# 04_PCIe.net
KiCad netlist of a schematic drawn in Altium Designer
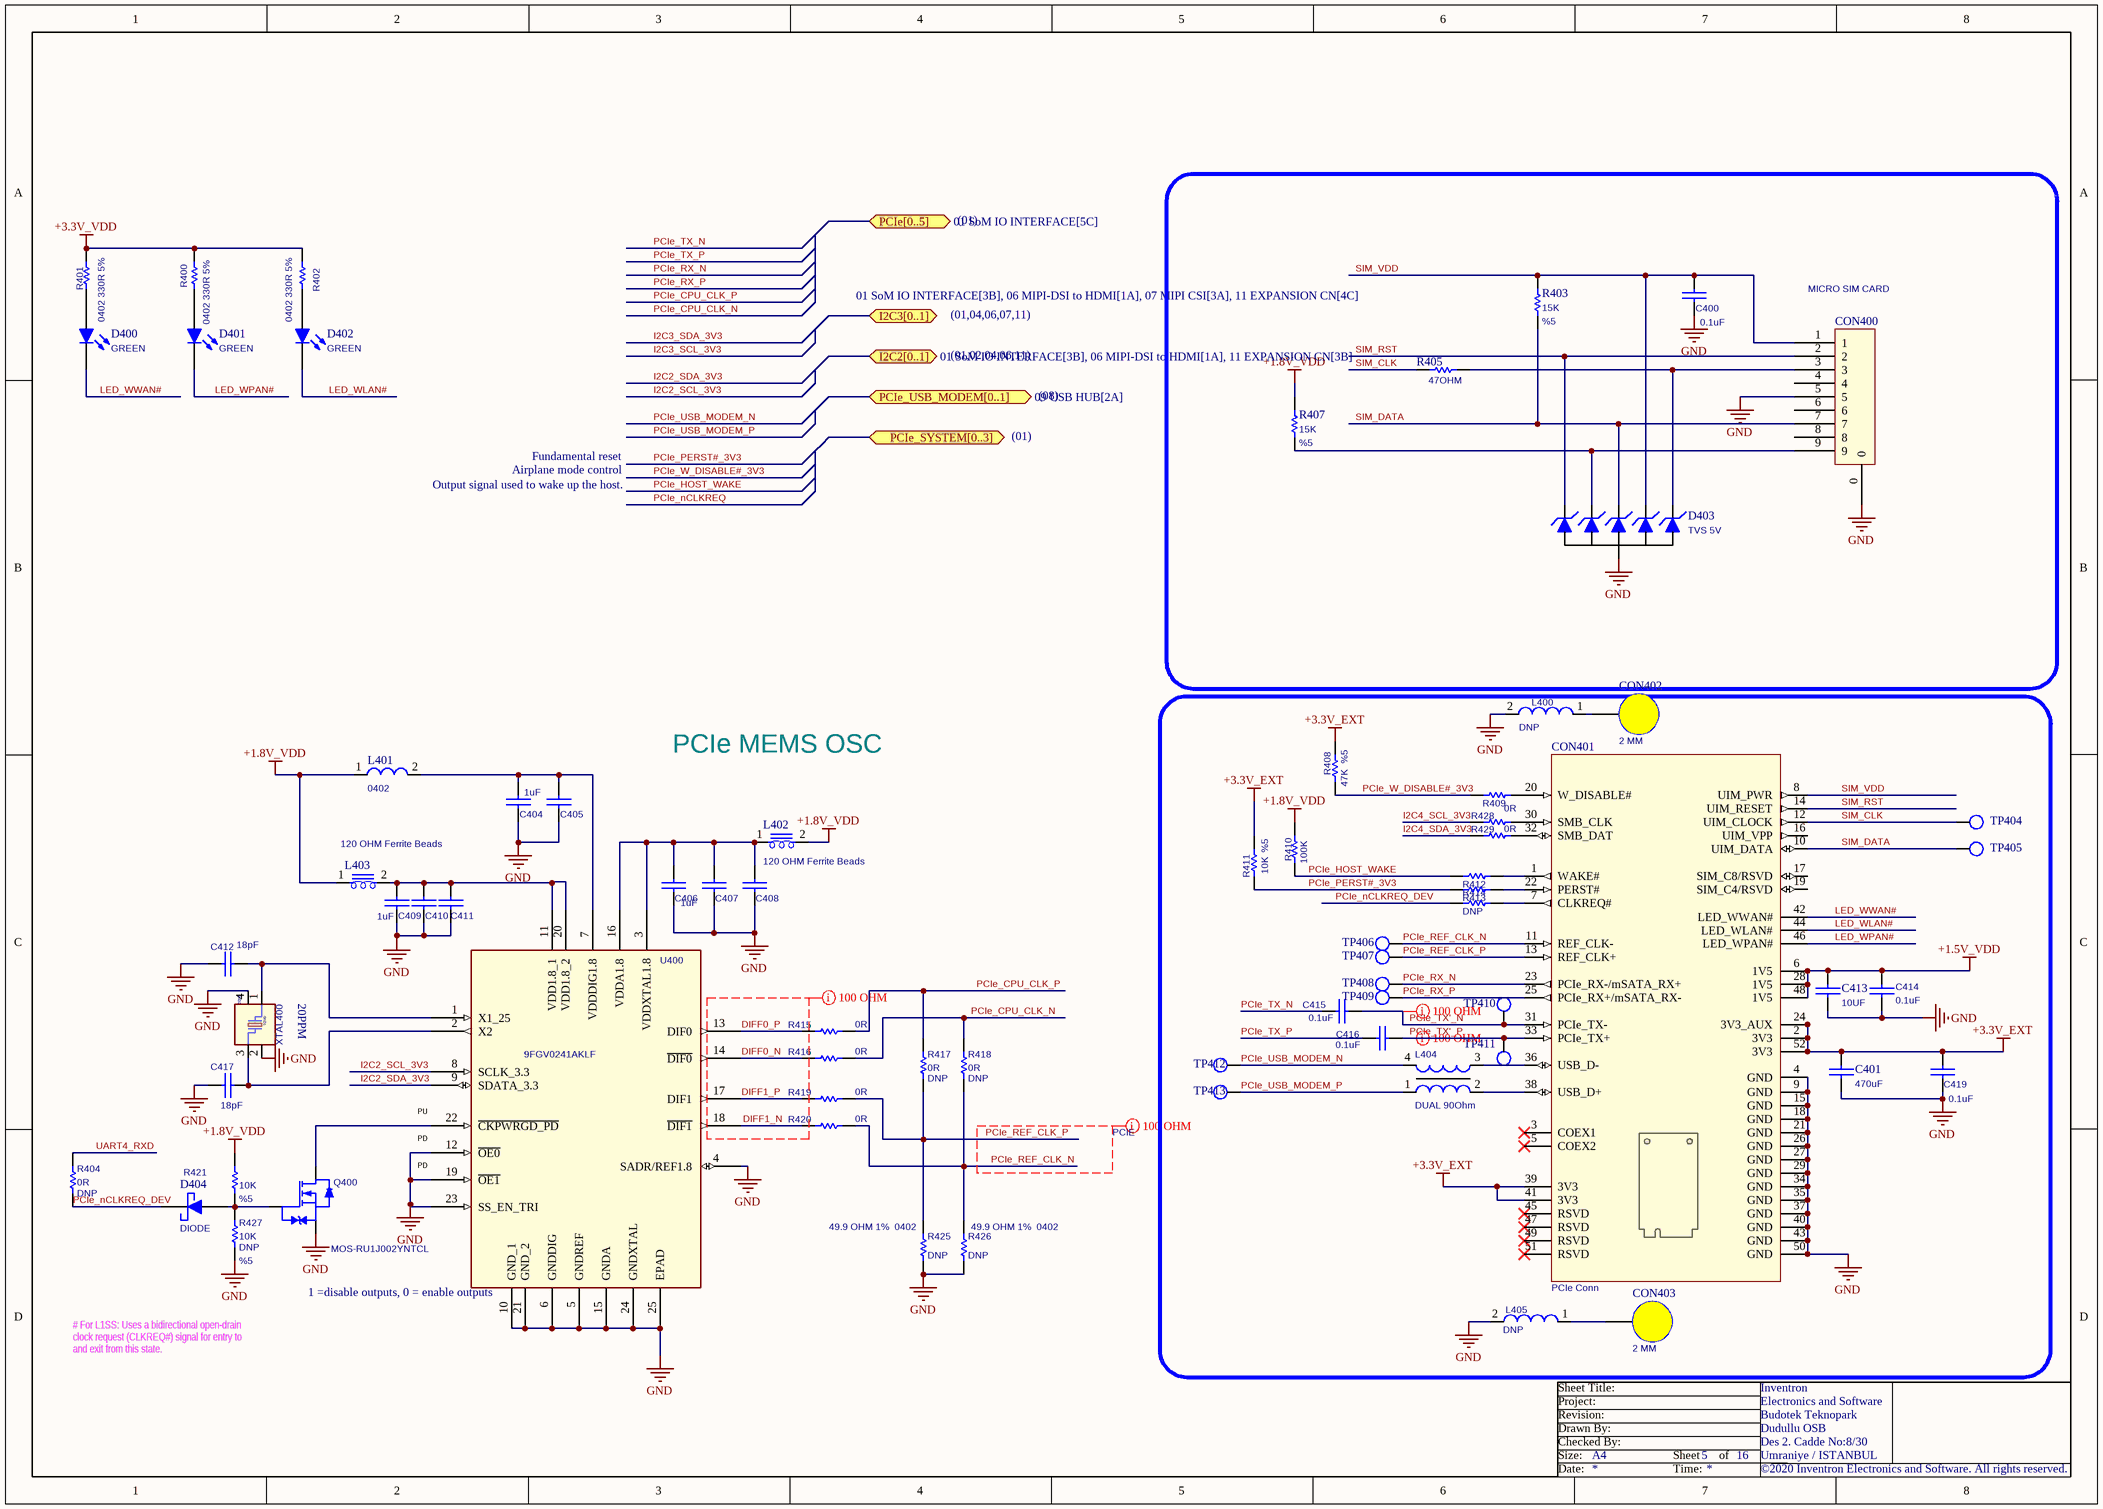
[diagram p0: 04 PCIe.SchDoc]

(export (version "E")
  (design (tool "Eeschema 10.0.6"))
  (components
    (comp (ref "C400")
      (value "0.1uF")
      (footprint "0402_CC")
      (description "CAP VER 0.1UF 16V X7R 0402")
      (fields (field (name "CREATED BY") "LA") (field (name "CHECKED BY") "*"))
      (libsource (lib "ARETE_SCH") (part "CAP-CL05B104KO5NNNC"))
    )
    (comp (ref "C401")
      (value "470uF")
      (footprint "CAP-8.3mm x 8.3mm")
      (description "CAP ALUM 470UF 20% 6.3V SMD")
      (fields (field (name "CREATED BY") "EE") (field (name "CHECKED BY") "*"))
      (libsource (lib "ARETE_SCH") (part "CAP-EEE-FP0J471AP"))
    )
    (comp (ref "C404")
      (value "1uF")
      (footprint "0402_CC")
      (description "CAP CER 1UF 6.3V X6S 0402")
      (fields (field (name "CREATED BY") "LA") (field (name "CHECKED BY") "*"))
      (libsource (lib "ARETE_SCH") (part "CAP-CL05X105KQ5NNNC"))
    )
    (comp (ref "C405")
      (value "0.01uF 16V 0402")
      (footprint "0402_CC")
      (description "CAP CER 10000PF 16V X7R 0402")
      (fields (field (name "CREATED BY") "E.E") (field (name "CHECKED BY") "*"))
      (libsource (lib "ARETE_SCH") (part "CAP-CL05B103KO5NNNC"))
    )
    (comp (ref "C406")
      (value "1uF")
      (footprint "0402_CC")
      (description "CAP CER 1UF 6.3V X6S 0402")
      (fields (field (name "CREATED BY") "LA") (field (name "CHECKED BY") "*"))
      (libsource (lib "ARETE_SCH") (part "CAP-CL05X105KQ5NNNC"))
    )
    (comp (ref "C407")
      (value "0.01uF 16V 0402")
      (footprint "0402_CC")
      (description "CAP CER 10000PF 16V X7R 0402")
      (fields (field (name "CREATED BY") "E.E") (field (name "CHECKED BY") "*"))
      (libsource (lib "ARETE_SCH") (part "CAP-CL05B103KO5NNNC"))
    )
    (comp (ref "C408")
      (value "0.01uF 16V 0402")
      (footprint "0402_CC")
      (description "CAP CER 10000PF 16V X7R 0402")
      (fields (field (name "CREATED BY") "E.E") (field (name "CHECKED BY") "*"))
      (libsource (lib "ARETE_SCH") (part "CAP-CL05B103KO5NNNC"))
    )
    (comp (ref "C409")
      (value "1uF")
      (footprint "0402_CC")
      (description "CAP CER 1UF 6.3V X6S 0402")
      (fields (field (name "CREATED BY") "LA") (field (name "CHECKED BY") "*"))
      (libsource (lib "ARETE_SCH") (part "CAP-CL05X105KQ5NNNC"))
    )
    (comp (ref "C410")
      (value "0.01uF 16V 0402")
      (footprint "0402_CC")
      (description "CAP CER 10000PF 16V X7R 0402")
      (fields (field (name "CREATED BY") "E.E") (field (name "CHECKED BY") "*"))
      (libsource (lib "ARETE_SCH") (part "CAP-CL05B103KO5NNNC"))
    )
    (comp (ref "C411")
      (value "0.01uF 16V 0402")
      (footprint "0402_CC")
      (description "CAP CER 10000PF 16V X7R 0402")
      (fields (field (name "CREATED BY") "E.E") (field (name "CHECKED BY") "*"))
      (libsource (lib "ARETE_SCH") (part "CAP-CL05B103KO5NNNC"))
    )
    (comp (ref "C412")
      (value "18pF")
      (footprint "0402_CC")
      (description "CAP CER 18PF 50V C0G/NPO 0402")
      (fields (field (name "CREATED BY") "LA") (field (name "CHECKED BY") "*"))
      (libsource (lib "ARETE_SCH") (part "CAP-CC0402JRNPO9BN180"))
    )
    (comp (ref "C413")
      (value "10UF")
      (footprint "0805")
      (description "CAP CER 10UF 16V X5R 0805")
      (fields (field (name "CREATED BY") "EE") (field (name "CHECKED BY") "*"))
      (libsource (lib "ARETE_SCH") (part "CAP-CL21A106KOQNNNG"))
    )
    (comp (ref "C414")
      (value "0.1uF")
      (footprint "0402_CC")
      (description "CAP VER 0.1UF 16V X7R 0402")
      (fields (field (name "CREATED BY") "LA") (field (name "CHECKED BY") "*"))
      (libsource (lib "ARETE_SCH") (part "CAP-CL05B104KO5NNNC"))
    )
    (comp (ref "C415")
      (value "0.1uF")
      (footprint "0402_CC")
      (description "CAP VER 0.1UF 16V X7R 0402")
      (fields (field (name "CREATED BY") "LA") (field (name "CHECKED BY") "*"))
      (libsource (lib "ARETE_SCH") (part "CAP-CL05B104KO5NNNC"))
    )
    (comp (ref "C416")
      (value "0.1uF")
      (footprint "0402_CC")
      (description "CAP VER 0.1UF 16V X7R 0402")
      (fields (field (name "CREATED BY") "LA") (field (name "CHECKED BY") "*"))
      (libsource (lib "ARETE_SCH") (part "CAP-CL05B104KO5NNNC"))
    )
    (comp (ref "C417")
      (value "18pF")
      (footprint "0402_CC")
      (description "CAP CER 18PF 50V C0G/NPO 0402")
      (fields (field (name "CREATED BY") "LA") (field (name "CHECKED BY") "*"))
      (libsource (lib "ARETE_SCH") (part "CAP-CC0402JRNPO9BN180"))
    )
    (comp (ref "C419")
      (value "0.1uF")
      (footprint "0402_CC")
      (description "CAP VER 0.1UF 16V X7R 0402")
      (fields (field (name "CREATED BY") "LA") (field (name "CHECKED BY") "*"))
      (libsource (lib "ARETE_SCH") (part "CAP-CL05B104KO5NNNC"))
    )
    (comp (ref "CON400")
      (value "MICRO SIM CARD")
      (footprint "115Q-BCA0")
      (description "CONN.MICRO SIM CARD PUSH PUSH 8+2 SMT WITH SWITCH")
      (fields (field (name "CREATED BY") "EE") (field (name "CHECKED BY") "*"))
      (libsource (lib "ARETE_SCH") (part "CON-115Q-BCA0"))
    )
    (comp (ref "CON401")
      (value "PCIe Conn")
      (footprint "PCIe MINI 52POS (2SCREW)")
      (description "CONN PCI EXP MINI FEMALE 52POS")
      (fields (field (name "CREATED BY") "E.E") (field (name "CHECKED BY") "*"))
      (libsource (lib "ARETE_SCH") (part "CON-2041262-1"))
    )
    (comp (ref "CON402")
      (value "2 MM")
      (footprint "9774045243R")
      (description "Round Standoff Threaded M2x0.4 Steel 0.177\" (4.50mm)")
      (fields (field (name "CREATED BY") "EE") (field (name "CHECKED BY") "*"))
      (libsource (lib "ARETE_SCH") (part "CON-9774045243R"))
    )
    (comp (ref "CON403")
      (value "2 MM")
      (footprint "9774045243R")
      (description "Round Standoff Threaded M2x0.4 Steel 0.177\" (4.50mm)")
      (fields (field (name "CREATED BY") "EE") (field (name "CHECKED BY") "*"))
      (libsource (lib "ARETE_SCH") (part "CON-9774045243R"))
    )
    (comp (ref "D400")
      (value "GREEN")
      (footprint "0603_LED")
      (description "LED SMD 0603 SUPER GREEN")
      (fields (field (name "CREATED BY") "*") (field (name "CHECKED BY") "*"))
      (libsource (lib "ARETE_SCH") (part "LED-LTST-C190KRKT"))
    )
    (comp (ref "D401")
      (value "GREEN")
      (footprint "0603_LED")
      (description "LED SMD 0603 SUPER GREEN")
      (fields (field (name "CREATED BY") "*") (field (name "CHECKED BY") "*"))
      (libsource (lib "ARETE_SCH") (part "LED-LTST-C190KRKT"))
    )
    (comp (ref "D402")
      (value "GREEN")
      (footprint "0603_LED")
      (description "LED SMD 0603 SUPER GREEN")
      (fields (field (name "CREATED BY") "*") (field (name "CHECKED BY") "*"))
      (libsource (lib "ARETE_SCH") (part "LED-LTST-C190KRKT"))
    )
    (comp (ref "D403")
      (value "TVS 5V")
      (footprint "SC-70")
      (description "TVS DIODE 5V 12.5V SC70-6")
      (fields (field (name "CREATED BY") "EE") (field (name "CHECKED BY") "*"))
      (libsource (lib "ARETE_SCH") (part "DIODE-SMF05C.TCT"))
    )
    (comp (ref "D404")
      (value "DIODE")
      (footprint "SOD-323")
      (description "Diode Schottky 1A (DC) Surface Mount SOD-323")
      (fields (field (name "CREATED BY") "E.E") (field (name "CHECKED BY") "*"))
      (libsource (lib "ARETE_SCH") (part "DIODE-NSR0320MW2T1G"))
    )
    (comp (ref "L400")
      (value "FERRITE 0603")
      (footprint "0603_RES")
      (description "FERRITE BEAD 0603")
      (fields (field (name "ASSY_OPT") "DNP") (field (name "CHECKED BY") "*"))
      (libsource (lib "ARETE_L") (part "IND-FERRITE 0603"))
    )
    (comp (ref "L401")
      (value "0402")
      (footprint "0402_RES")
      (description "0OHM 0402")
      (fields (field (name "CREATED BY") "EE") (field (name "CHECKED BY") "*"))
      (libsource (lib "ARETE_SCH") (part "IND-FERRITE (RES 0 OHM) 0402"))
    )
    (comp (ref "L402")
      (value "120 OHM Ferrite Beads")
      (footprint "0603_RES")
      (description "Ferrite Beads Multi-Layer 120Ohm 25% 100MHz 2A 0.05Ohm DCR 0603 Automotive T/R")
      (fields (field (name "CREATED BY") "E.E") (field (name "CHECKED BY") "*"))
      (libsource (lib "ARETE_SCH") (part "IND-BLM18PG121SH1D"))
    )
    (comp (ref "L403")
      (value "120 OHM Ferrite Beads")
      (footprint "0603_RES")
      (description "Ferrite Beads Multi-Layer 120Ohm 25% 100MHz 2A 0.05Ohm DCR 0603 Automotive T/R")
      (fields (field (name "CREATED BY") "E.E") (field (name "CHECKED BY") "*"))
      (libsource (lib "ARETE_SCH") (part "IND-BLM18PG121SH1D"))
    )
    (comp (ref "L404")
      (value "DUAL 90Ohm")
      (footprint "DLW21H")
      (description "Common Mode Chokes Dual 90Ohm 100MHz 0.33A 0.35Ohm DCR SMD T/R")
      (fields (field (name "CREATED BY") "E.E") (field (name "CHECKED BY") "*"))
      (libsource (lib "ARETE_SCH") (part "IND-DLW21HN900SQ2L"))
    )
    (comp (ref "L405")
      (value "FERRITE 0603")
      (footprint "0603_RES")
      (description "FERRITE BEAD 0603")
      (fields (field (name "ASSY_OPT") "DNP") (field (name "CHECKED BY") "*"))
      (libsource (lib "ARETE_L") (part "IND-FERRITE 0603"))
    )
    (comp (ref "Q400")
      (value "MOS-RU1J002YNTCL")
      (footprint "SC-85-3/SOT-323FL")
      (description "MOSFET N-CH 50V 0.2A UMT3F")
      (fields (field (name "CREATED BY") "LA") (field (name "CHECKED BY") "*"))
      (libsource (lib "ARETE_SCH") (part "MOS-RU1J002YNTCL"))
    )
    (comp (ref "R400")
      (value "0402 330R 5%")
      (footprint "0402_RES")
      (fields
        (field (name "TOLERANCE") "%5")
        (field (name "CREATED BY") "E.E")
        (field (name "CHECKED BY") "*")
      )
      (libsource (lib "ARETE_L") (part "RES-CRGCQ0402J330R"))
    )
    (comp (ref "R401")
      (value "0402 330R 5%")
      (footprint "0402_RES")
      (fields
        (field (name "TOLERANCE") "%5")
        (field (name "CREATED BY") "E.E")
        (field (name "CHECKED BY") "*")
      )
      (libsource (lib "ARETE_L") (part "RES-CRGCQ0402J330R"))
    )
    (comp (ref "R402")
      (value "0402 330R 5%")
      (footprint "0402_RES")
      (fields
        (field (name "TOLERANCE") "%5")
        (field (name "CREATED BY") "E.E")
        (field (name "CHECKED BY") "*")
      )
      (libsource (lib "ARETE_L") (part "RES-CRGCQ0402J330R"))
    )
    (comp (ref "R403")
      (value "15K")
      (footprint "0402_RES")
      (description "RES 15K OHM 5% 1/16W 0402")
      (fields
        (field (name "TOLERANCE") "%5")
        (field (name "CREATED BY") "LA")
        (field (name "CHECKED BY") "*")
      )
      (libsource (lib "ARETE_SCH") (part "RES-RMCF0402JT15K0"))
    )
    (comp (ref "R404")
      (value "0R")
      (footprint "0402_RES")
      (description "RES 0 OHM JUMPER 1/16W 0402")
      (fields
        (field (name "ASSY_OPT") "DNP")
        (field (name "CREATED BY") "LA")
        (field (name "CHECKED BY") "*")
      )
      (libsource (lib "ARETE_SCH") (part "RES-RMCF0402ZT0R00"))
    )
    (comp (ref "R405")
      (value "47OHM")
      (footprint "0402_RES")
      (description "RES SMD 47 OHM 5% 1/16W 0402")
      (fields (field (name "CREATED BY") "EE") (field (name "CHECKED BY") "*"))
      (libsource (lib "ARETE_SCH") (part "RES-RC0402JR-0747RL"))
    )
    (comp (ref "R407")
      (value "15K")
      (footprint "0402_RES")
      (description "RES 15K OHM 5% 1/16W 0402")
      (fields
        (field (name "TOLERANCE") "%5")
        (field (name "CREATED BY") "LA")
        (field (name "CHECKED BY") "*")
      )
      (libsource (lib "ARETE_SCH") (part "RES-RMCF0402JT15K0"))
    )
    (comp (ref "R408")
      (value "47K")
      (footprint "0402_RES")
      (description "RES 47K OHM 5% 1/16W 0402")
      (fields
        (field (name "TOLERANCE") "%5")
        (field (name "CREATED BY") "LA")
        (field (name "CHECKED BY") "*")
      )
      (libsource (lib "ARETE_SCH") (part "RES-47K"))
    )
    (comp (ref "R409")
      (value "0402 330R 5%")
      (footprint "0402_RES")
      (fields
        (field (name "TOLERANCE") "%5")
        (field (name "CREATED BY") "E.E")
        (field (name "CHECKED BY") "*")
      )
      (libsource (lib "ARETE_SCH") (part "RES-CRGCQ0402J330R"))
    )
    (comp (ref "R410")
      (value "100K")
      (footprint "0402_RES")
      (description "RES 100K OHM 5% 1/16W 0402")
      (fields
        (field (name "TOLERANCE") "%5")
        (field (name "CREATED BY") "LA")
        (field (name "CHECKED BY") "*")
      )
      (libsource (lib "ARETE_SCH") (part "RES-RMCF0402JT100K"))
    )
    (comp (ref "R411")
      (value "10K")
      (footprint "0402_RES")
      (description "RES 10K OHM 5% 1/16W 0402")
      (fields
        (field (name "TOLERANCE") "%5")
        (field (name "CREATED BY") "LA")
        (field (name "CHECKED BY") "*")
      )
      (libsource (lib "ARETE_SCH") (part "RES-RMCF0402JT10K0"))
    )
    (comp (ref "R412")
      (value "0402 330R 5%")
      (footprint "0402_RES")
      (fields
        (field (name "TOLERANCE") "%5")
        (field (name "CREATED BY") "E.E")
        (field (name "CHECKED BY") "*")
      )
      (libsource (lib "ARETE_SCH") (part "RES-CRGCQ0402J330R"))
    )
    (comp (ref "R413")
      (value "0402 330R 5%")
      (footprint "0402_RES")
      (fields
        (field (name "TOLERANCE") "%5")
        (field (name "CREATED BY") "E.E")
        (field (name "CHECKED BY") "*")
      )
      (libsource (lib "ARETE_SCH") (part "RES-CRGCQ0402J330R"))
    )
    (comp (ref "R414")
      (value "0402 330R 5%")
      (footprint "0402_RES")
      (fields
        (field (name "ASSY_OPT") "DNP")
        (field (name "TOLERANCE") "%5")
        (field (name "CREATED BY") "E.E")
        (field (name "CHECKED BY") "*")
      )
      (libsource (lib "ARETE_SCH") (part "RES-CRGCQ0402J330R"))
    )
    (comp (ref "R415")
      (value "0R")
      (footprint "0402_RES")
      (description "RES 0 OHM JUMPER 1/16W 0402")
      (fields (field (name "CREATED BY") "LA") (field (name "CHECKED BY") "*"))
      (libsource (lib "ARETE_SCH") (part "RES-RMCF0402ZT0R00"))
    )
    (comp (ref "R416")
      (value "0R")
      (footprint "0402_RES")
      (description "RES 0 OHM JUMPER 1/16W 0402")
      (fields (field (name "CREATED BY") "LA") (field (name "CHECKED BY") "*"))
      (libsource (lib "ARETE_SCH") (part "RES-RMCF0402ZT0R00"))
    )
    (comp (ref "R417")
      (value "0R")
      (footprint "0402_RES")
      (description "RES 0 OHM JUMPER 1/16W 0402")
      (fields
        (field (name "ASSY_OPT") "DNP")
        (field (name "CREATED BY") "LA")
        (field (name "CHECKED BY") "*")
      )
      (libsource (lib "ARETE_SCH") (part "RES-RMCF0402ZT0R00"))
    )
    (comp (ref "R418")
      (value "0R")
      (footprint "0402_RES")
      (description "RES 0 OHM JUMPER 1/16W 0402")
      (fields
        (field (name "ASSY_OPT") "DNP")
        (field (name "CREATED BY") "LA")
        (field (name "CHECKED BY") "*")
      )
      (libsource (lib "ARETE_SCH") (part "RES-RMCF0402ZT0R00"))
    )
    (comp (ref "R419")
      (value "0R")
      (footprint "0402_RES")
      (description "RES 0 OHM JUMPER 1/16W 0402")
      (fields (field (name "CREATED BY") "LA") (field (name "CHECKED BY") "*"))
      (libsource (lib "ARETE_SCH") (part "RES-RMCF0402ZT0R00"))
    )
    (comp (ref "R420")
      (value "0R")
      (footprint "0402_RES")
      (description "RES 0 OHM JUMPER 1/16W 0402")
      (fields (field (name "CREATED BY") "LA") (field (name "CHECKED BY") "*"))
      (libsource (lib "ARETE_SCH") (part "RES-RMCF0402ZT0R00"))
    )
    (comp (ref "R421")
      (value "10K")
      (footprint "0402_RES")
      (description "RES 10K OHM 5% 1/16W 0402")
      (fields
        (field (name "TOLERANCE") "%5")
        (field (name "CREATED BY") "LA")
        (field (name "CHECKED BY") "*")
      )
      (libsource (lib "ARETE_SCH") (part "RES-RMCF0402JT10K0"))
    )
    (comp (ref "R425")
      (value "49.9 OHM 1%  0402")
      (footprint "0402_RES")
      (description "49.9 ±1% 0.063W, 1/16W Chip Resistor 0402 (1005 Metric) - Thick Film")
      (fields
        (field (name "ASSY_OPT") "DNP")
        (field (name "TOLERANCE") "±1%")
        (field (name "CREATED BY") "E.E")
        (field (name "CHECKED BY") "*")
      )
      (libsource (lib "ARETE_SCH") (part "RES-CR0402-FX-49R9GLF"))
    )
    (comp (ref "R426")
      (value "49.9 OHM 1%  0402")
      (footprint "0402_RES")
      (description "49.9 ±1% 0.063W, 1/16W Chip Resistor 0402 (1005 Metric) - Thick Film")
      (fields
        (field (name "ASSY_OPT") "DNP")
        (field (name "TOLERANCE") "±1%")
        (field (name "CREATED BY") "E.E")
        (field (name "CHECKED BY") "*")
      )
      (libsource (lib "ARETE_SCH") (part "RES-CR0402-FX-49R9GLF"))
    )
    (comp (ref "R427")
      (value "10K")
      (footprint "0402_RES")
      (description "RES 10K OHM 5% 1/16W 0402")
      (fields
        (field (name "ASSY_OPT") "DNP")
        (field (name "TOLERANCE") "%5")
        (field (name "CREATED BY") "LA")
        (field (name "CHECKED BY") "*")
      )
      (libsource (lib "ARETE_SCH") (part "RES-RMCF0402JT10K0"))
    )
    (comp (ref "R428")
      (value "0R")
      (footprint "0402_RES")
      (description "RES 0 OHM JUMPER 1/16W 0402")
      (fields (field (name "CREATED BY") "LA") (field (name "CHECKED BY") "*"))
      (libsource (lib "ARETE_SCH") (part "RES-RMCF0402ZT0R00"))
    )
    (comp (ref "R429")
      (value "0R")
      (footprint "0402_RES")
      (description "RES 0 OHM JUMPER 1/16W 0402")
      (fields (field (name "CREATED BY") "LA") (field (name "CHECKED BY") "*"))
      (libsource (lib "ARETE_SCH") (part "RES-RMCF0402ZT0R00"))
    )
    (comp (ref "TP404")
      (value "TEST POINT 15")
      (footprint "testpoint_15")
      (libsource (lib "ARETE_L") (part "TEST POINT 15"))
    )
    (comp (ref "TP405")
      (value "TEST POINT 15")
      (footprint "testpoint_15")
      (libsource (lib "ARETE_L") (part "TEST POINT 15"))
    )
    (comp (ref "TP406")
      (value "TEST POINT 15")
      (footprint "testpoint_15")
      (libsource (lib "ARETE_L") (part "TEST POINT 15"))
    )
    (comp (ref "TP407")
      (value "TEST POINT 15")
      (footprint "testpoint_15")
      (libsource (lib "ARETE_L") (part "TEST POINT 15"))
    )
    (comp (ref "TP408")
      (value "TEST POINT 15")
      (footprint "testpoint_15")
      (libsource (lib "ARETE_L") (part "TEST POINT 15"))
    )
    (comp (ref "TP409")
      (value "TEST POINT 15")
      (footprint "testpoint_15")
      (libsource (lib "ARETE_L") (part "TEST POINT 15"))
    )
    (comp (ref "TP410")
      (value "TEST POINT 35")
      (footprint "testpoint_15")
      (libsource (lib "ARETE_SCH") (part "TEST POINT 35"))
    )
    (comp (ref "TP411")
      (value "TEST POINT 35")
      (footprint "testpoint_15")
      (libsource (lib "ARETE_SCH") (part "TEST POINT 35"))
    )
    (comp (ref "TP412")
      (value "TEST POINT 15")
      (footprint "testpoint_15")
      (libsource (lib "ARETE_L") (part "TEST POINT 15"))
    )
    (comp (ref "TP413")
      (value "TEST POINT 15")
      (footprint "testpoint_15")
      (libsource (lib "ARETE_L") (part "TEST POINT 15"))
    )
    (comp (ref "U400")
      (value "9FGV0241AKLF")
      (footprint "9FGV0241AKLF")
      (description "IC CLOCK GENERATOR 24VFQFPN")
      (fields (field (name "CREATED BY") "E.E") (field (name "CHECKED BY") "*"))
      (libsource (lib "ARETE_SCH") (part "IC-9FGV0241AKLF"))
    )
    (comp (ref "XTAL400")
      (value "XTAL-TSX-3225 25.0000MF10P-C0")
      (footprint "XTLOSC4_3P2X2P5MM_SM")
      (description "CRYSTAL 25.0000MHZ 18PF SMD")
      (fields (field (name "CREATED BY") "E.E") (field (name "CHECKED BY") "*"))
      (libsource (lib "ARETE_SCH") (part "XTAL-TSX-3225 25.0000MF10P-C0"))
    )
  )
  (nets
    (net (code "17") (name "+1.5V_VDD") (class "Default")
      (node (ref "C413") (pin "1") (pinfunction "1_1") (pintype "passive"))
      (node (ref "C414") (pin "2") (pinfunction "2_2") (pintype "passive"))
      (node (ref "CON401") (pin "28") (pinfunction "1V5_28") (pintype "power_in"))
      (node (ref "CON401") (pin "48") (pinfunction "1V5_48") (pintype "power_in"))
      (node (ref "CON401") (pin "6") (pinfunction "1V5_6") (pintype "power_in"))
    )
    (net (code "18") (name "+1.8V_VDD") (class "Default")
      (node (ref "L401") (pin "1") (pinfunction "1_1") (pintype "passive"))
      (node (ref "L402") (pin "2") (pinfunction "2_2") (pintype "passive"))
      (node (ref "L403") (pin "1") (pinfunction "1_1") (pintype "passive"))
      (node (ref "R407") (pin "2") (pinfunction "2_2") (pintype "passive"))
      (node (ref "R410") (pin "2") (pinfunction "2_2") (pintype "passive"))
      (node (ref "R421") (pin "2") (pinfunction "2_2") (pintype "passive"))
    )
    (net (code "19") (name "+3.3V_EXT") (class "Default")
      (node (ref "C401") (pin "1") (pinfunction "1_1") (pintype "passive"))
      (node (ref "C419") (pin "1") (pinfunction "1_1") (pintype "passive"))
      (node (ref "CON401") (pin "2") (pinfunction "3V3_2") (pintype "power_in"))
      (node (ref "CON401") (pin "24") (pinfunction "3V3_AUX_24") (pintype "power_in"))
      (node (ref "CON401") (pin "39") (pinfunction "3V3_39") (pintype "passive"))
      (node (ref "CON401") (pin "41") (pinfunction "3V3_41") (pintype "passive"))
      (node (ref "CON401") (pin "52") (pinfunction "3V3_52") (pintype "power_in"))
      (node (ref "R408") (pin "2") (pinfunction "2_2") (pintype "passive"))
      (node (ref "R411") (pin "2") (pinfunction "2_2") (pintype "passive"))
    )
    (net (code "20") (name "+3.3V_VDD") (class "Default")
      (node (ref "R400") (pin "2") (pinfunction "2_2") (pintype "passive"))
      (node (ref "R401") (pin "2") (pinfunction "2_2") (pintype "passive"))
      (node (ref "R402") (pin "2") (pinfunction "2_2") (pintype "passive"))
    )
    (net (code "21") (name "/DIFF0_N") (class "Default")
      (node (ref "R416") (pin "1") (pinfunction "1_1") (pintype "passive"))
      (node (ref "U400") (pin "14") (pinfunction "~{DIF0}_14") (pintype "output"))
    )
    (net (code "22") (name "/DIFF0_P") (class "Default")
      (node (ref "R415") (pin "1") (pinfunction "1_1") (pintype "passive"))
      (node (ref "U400") (pin "13") (pinfunction "DIF0_13") (pintype "output"))
    )
    (net (code "23") (name "/DIFF1_N") (class "Default")
      (node (ref "R420") (pin "1") (pinfunction "1_1") (pintype "passive"))
      (node (ref "U400") (pin "18") (pinfunction "~{DIF1}_18") (pintype "output"))
    )
    (net (code "24") (name "/DIFF1_P") (class "Default")
      (node (ref "R419") (pin "1") (pinfunction "1_1") (pintype "passive"))
      (node (ref "U400") (pin "17") (pinfunction "DIF1_17") (pintype "output"))
    )
    (net (code "26") (name "/I2C2_SCL_3V3") (class "Default")
      (node (ref "U400") (pin "8") (pinfunction "SCLK_3.3_8") (pintype "input"))
    )
    (net (code "27") (name "/I2C2_SDA_3V3") (class "Default")
      (node (ref "U400") (pin "9") (pinfunction "SDATA_3.3_9") (pintype "bidirectional"))
    )
    (net (code "31") (name "/I2C4_SCL_3V3") (class "Default")
      (node (ref "R428") (pin "1") (pinfunction "1_1") (pintype "passive"))
    )
    (net (code "32") (name "/I2C4_SDA_3V3") (class "Default")
      (node (ref "R429") (pin "1") (pinfunction "1_1") (pintype "passive"))
    )
    (net (code "33") (name "/LED_WLAN#") (class "Default")
      (node (ref "CON401") (pin "44") (pinfunction "LED_WLAN#_44") (pintype "open_collector"))
      (node (ref "D402") (pin "2") (pinfunction "K_2") (pintype "passive"))
    )
    (net (code "34") (name "/LED_WPAN#") (class "Default")
      (node (ref "CON401") (pin "46") (pinfunction "LED_WPAN#_46") (pintype "open_collector"))
      (node (ref "D401") (pin "2") (pinfunction "K_2") (pintype "passive"))
    )
    (net (code "35") (name "/LED_WWAN#") (class "Default")
      (node (ref "CON401") (pin "42") (pinfunction "LED_WWAN#_42") (pintype "open_collector"))
      (node (ref "D400") (pin "2") (pinfunction "K_2") (pintype "passive"))
    )
    (net (code "37") (name "/PCIe_CPU_CLK_N") (class "Default")
      (node (ref "R416") (pin "2") (pinfunction "2_2") (pintype "passive"))
      (node (ref "R418") (pin "2") (pinfunction "2_2") (pintype "passive"))
    )
    (net (code "38") (name "/PCIe_CPU_CLK_P") (class "Default")
      (node (ref "R415") (pin "2") (pinfunction "2_2") (pintype "passive"))
      (node (ref "R417") (pin "2") (pinfunction "2_2") (pintype "passive"))
    )
    (net (code "39") (name "/PCIe_HOST_WAKE") (class "Default")
      (node (ref "R410") (pin "1") (pinfunction "1_1") (pintype "passive"))
      (node (ref "R412") (pin "2") (pinfunction "2_2") (pintype "passive"))
    )
    (net (code "40") (name "/PCIe_PERST#_3V3") (class "Default")
      (node (ref "R411") (pin "1") (pinfunction "1_1") (pintype "passive"))
      (node (ref "R413") (pin "2") (pinfunction "2_2") (pintype "passive"))
    )
    (net (code "41") (name "/PCIe_REF_CLK_N") (class "Default")
      (node (ref "CON401") (pin "11") (pinfunction "REF_CLK-_11") (pintype "input"))
      (node (ref "R418") (pin "1") (pinfunction "1_1") (pintype "passive"))
      (node (ref "R420") (pin "2") (pinfunction "2_2") (pintype "passive"))
      (node (ref "R426") (pin "2") (pinfunction "2_2") (pintype "passive"))
      (node (ref "TP406") (pin "1") (pinfunction "1_1") (pintype "passive"))
    )
    (net (code "42") (name "/PCIe_REF_CLK_P") (class "Default")
      (node (ref "CON401") (pin "13") (pinfunction "REF_CLK+_13") (pintype "input"))
      (node (ref "R417") (pin "1") (pinfunction "1_1") (pintype "passive"))
      (node (ref "R419") (pin "2") (pinfunction "2_2") (pintype "passive"))
      (node (ref "R425") (pin "2") (pinfunction "2_2") (pintype "passive"))
      (node (ref "TP407") (pin "1") (pinfunction "1_1") (pintype "passive"))
    )
    (net (code "43") (name "/PCIe_RX_N") (class "Default")
      (node (ref "CON401") (pin "23") (pinfunction "PCIe_RX-/mSATA_RX+_23") (pintype "output"))
      (node (ref "TP408") (pin "1") (pinfunction "1_1") (pintype "passive"))
    )
    (net (code "44") (name "/PCIe_RX_P") (class "Default")
      (node (ref "CON401") (pin "25") (pinfunction "PCIe_RX+/mSATA_RX-_25") (pintype "output"))
      (node (ref "TP409") (pin "1") (pinfunction "1_1") (pintype "passive"))
    )
    (net (code "46") (name "/PCIe_TX'_N") (class "Default")
      (node (ref "C415") (pin "2") (pinfunction "2_2") (pintype "passive"))
      (node (ref "CON401") (pin "31") (pinfunction "PCIe_TX-_31") (pintype "input"))
      (node (ref "TP410") (pin "1") (pinfunction "1_1") (pintype "passive"))
    )
    (net (code "47") (name "/PCIe_TX'_P") (class "Default")
      (node (ref "C416") (pin "2") (pinfunction "2_2") (pintype "passive"))
      (node (ref "CON401") (pin "33") (pinfunction "PCIe_TX+_33") (pintype "input"))
      (node (ref "TP411") (pin "1") (pinfunction "1_1") (pintype "passive"))
    )
    (net (code "48") (name "/PCIe_TX_N") (class "Default")
      (node (ref "C415") (pin "1") (pinfunction "1_1") (pintype "passive"))
    )
    (net (code "49") (name "/PCIe_TX_P") (class "Default")
      (node (ref "C416") (pin "1") (pinfunction "1_1") (pintype "passive"))
    )
    (net (code "51") (name "/PCIe_USB_MODEM_N") (class "Default")
      (node (ref "L404") (pin "4") (pinfunction "4_4") (pintype "passive"))
      (node (ref "TP412") (pin "1") (pinfunction "1_1") (pintype "passive"))
    )
    (net (code "52") (name "/PCIe_USB_MODEM_P") (class "Default")
      (node (ref "L404") (pin "1") (pinfunction "1_1") (pintype "passive"))
      (node (ref "TP413") (pin "1") (pinfunction "1_1") (pintype "passive"))
    )
    (net (code "53") (name "/PCIe_W_DISABLE#_3V3") (class "Default")
      (node (ref "R408") (pin "1") (pinfunction "1_1") (pintype "passive"))
      (node (ref "R409") (pin "2") (pinfunction "2_2") (pintype "passive"))
    )
    (net (code "55") (name "/PCIe_nCLKREQ_DEV") (class "Default")
      (node (ref "D404") (pin "K") (pinfunction "K_K") (pintype "passive"))
      (node (ref "R404") (pin "1") (pinfunction "1_1") (pintype "passive"))
      (node (ref "R414") (pin "2") (pinfunction "2_2") (pintype "passive"))
    )
    (net (code "56") (name "/SIM_CLK") (class "Default")
      (node (ref "CON401") (pin "12") (pinfunction "UIM_CLOCK_12") (pintype "output"))
      (node (ref "R405") (pin "1") (pinfunction "1_1") (pintype "passive"))
      (node (ref "TP404") (pin "1") (pinfunction "1_1") (pintype "passive"))
    )
    (net (code "57") (name "/SIM_DATA") (class "Default")
      (node (ref "CON400") (pin "7") (pinfunction "7_7") (pintype "passive"))
      (node (ref "CON401") (pin "10") (pinfunction "UIM_DATA_10") (pintype "bidirectional"))
      (node (ref "D403") (pin "4") (pinfunction "4_4") (pintype "passive"))
      (node (ref "R403") (pin "1") (pinfunction "1_1") (pintype "passive"))
      (node (ref "TP405") (pin "1") (pinfunction "1_1") (pintype "passive"))
    )
    (net (code "58") (name "/SIM_RST") (class "Default")
      (node (ref "CON400") (pin "2") (pinfunction "2_2") (pintype "passive"))
      (node (ref "CON401") (pin "14") (pinfunction "UIM_RESET_14") (pintype "output"))
      (node (ref "D403") (pin "1") (pinfunction "1_1") (pintype "passive"))
    )
    (net (code "59") (name "/SIM_VDD") (class "Default")
      (node (ref "C400") (pin "1") (pinfunction "1_1") (pintype "passive"))
      (node (ref "CON400") (pin "1") (pinfunction "1_1") (pintype "passive"))
      (node (ref "CON401") (pin "8") (pinfunction "UIM_PWR_8") (pintype "output"))
      (node (ref "D403") (pin "5") (pinfunction "5_5") (pintype "passive"))
      (node (ref "R403") (pin "2") (pinfunction "2_2") (pintype "passive"))
    )
    (net (code "60") (name "/UART4_RXD") (class "Default")
      (node (ref "R404") (pin "2") (pinfunction "2_2") (pintype "passive"))
    )
    (net (code "61") (name "GND") (class "Default")
      (node (ref "C400") (pin "2") (pinfunction "2_2") (pintype "passive"))
      (node (ref "C401") (pin "2") (pinfunction "2_2") (pintype "passive"))
      (node (ref "C404") (pin "2") (pinfunction "2_2") (pintype "passive"))
      (node (ref "C405") (pin "2") (pinfunction "2_2") (pintype "passive"))
      (node (ref "C406") (pin "2") (pinfunction "2_2") (pintype "passive"))
      (node (ref "C407") (pin "2") (pinfunction "2_2") (pintype "passive"))
      (node (ref "C408") (pin "2") (pinfunction "2_2") (pintype "passive"))
      (node (ref "C409") (pin "2") (pinfunction "2_2") (pintype "passive"))
      (node (ref "C410") (pin "2") (pinfunction "2_2") (pintype "passive"))
      (node (ref "C411") (pin "2") (pinfunction "2_2") (pintype "passive"))
      (node (ref "C412") (pin "1") (pinfunction "1_1") (pintype "passive"))
      (node (ref "C413") (pin "2") (pinfunction "2_2") (pintype "passive"))
      (node (ref "C414") (pin "1") (pinfunction "1_1") (pintype "passive"))
      (node (ref "C417") (pin "1") (pinfunction "1_1") (pintype "passive"))
      (node (ref "C419") (pin "2") (pinfunction "2_2") (pintype "passive"))
      (node (ref "CON400") (pin "0") (pinfunction "0_0") (pintype "passive"))
      (node (ref "CON400") (pin "5") (pinfunction "5_5") (pintype "passive"))
      (node (ref "CON401") (pin "15") (pinfunction "GND_15") (pintype "power_in"))
      (node (ref "CON401") (pin "18") (pinfunction "GND_18") (pintype "power_in"))
      (node (ref "CON401") (pin "21") (pinfunction "GND_21") (pintype "power_in"))
      (node (ref "CON401") (pin "26") (pinfunction "GND_26") (pintype "power_in"))
      (node (ref "CON401") (pin "27") (pinfunction "GND_27") (pintype "power_in"))
      (node (ref "CON401") (pin "29") (pinfunction "GND_29") (pintype "power_in"))
      (node (ref "CON401") (pin "34") (pinfunction "GND_34") (pintype "power_in"))
      (node (ref "CON401") (pin "35") (pinfunction "GND_35") (pintype "power_in"))
      (node (ref "CON401") (pin "37") (pinfunction "GND_37") (pintype "power_in"))
      (node (ref "CON401") (pin "4") (pinfunction "GND_4") (pintype "power_in"))
      (node (ref "CON401") (pin "40") (pinfunction "GND_40") (pintype "power_in"))
      (node (ref "CON401") (pin "43") (pinfunction "GND_43") (pintype "power_in"))
      (node (ref "CON401") (pin "50") (pinfunction "GND_50") (pintype "power_in"))
      (node (ref "CON401") (pin "9") (pinfunction "GND_9") (pintype "power_in"))
      (node (ref "D403") (pin "2") (pinfunction "2_2") (pintype "passive"))
      (node (ref "L400") (pin "2") (pinfunction "2_2") (pintype "passive"))
      (node (ref "L405") (pin "2") (pinfunction "2_2") (pintype "passive"))
      (node (ref "Q400") (pin "2") (pinfunction "S_2") (pintype "passive"))
      (node (ref "R425") (pin "1") (pinfunction "1_1") (pintype "passive"))
      (node (ref "R426") (pin "1") (pinfunction "1_1") (pintype "passive"))
      (node (ref "R427") (pin "1") (pinfunction "1_1") (pintype "passive"))
      (node (ref "U400") (pin "10") (pinfunction "GND_1_10") (pintype "power_in"))
      (node (ref "U400") (pin "12") (pinfunction "~{OE0}_12") (pintype "input"))
      (node (ref "U400") (pin "15") (pinfunction "GNDA_15") (pintype "power_in"))
      (node (ref "U400") (pin "19") (pinfunction "~{OE1}_19") (pintype "input"))
      (node (ref "U400") (pin "21") (pinfunction "GND_2_21") (pintype "power_in"))
      (node (ref "U400") (pin "23") (pinfunction "SS_EN_TRI_23") (pintype "input"))
      (node (ref "U400") (pin "24") (pinfunction "GNDXTAL_24") (pintype "power_in"))
      (node (ref "U400") (pin "25") (pinfunction "EPAD_25") (pintype "power_in"))
      (node (ref "U400") (pin "4") (pinfunction "SADR/REF1.8_4") (pintype "bidirectional"))
      (node (ref "U400") (pin "5") (pinfunction "GNDREF_5") (pintype "power_in"))
      (node (ref "U400") (pin "6") (pinfunction "GNDDIG_6") (pintype "power_in"))
      (node (ref "XTAL400") (pin "2") (pinfunction "GND1_2") (pintype "power_in"))
      (node (ref "XTAL400") (pin "4") (pinfunction "GND2_4") (pintype "power_in"))
    )
    (net (code "62") (name "Net-(CON400-Pad3)") (class "Default")
      (node (ref "CON400") (pin "3") (pinfunction "3_3") (pintype "passive"))
      (node (ref "D403") (pin "6") (pinfunction "6_6") (pintype "passive"))
      (node (ref "R405") (pin "2") (pinfunction "2_2") (pintype "passive"))
    )
    (net (code "63") (name "Net-(CON400-Pad9)") (class "Default")
      (node (ref "CON400") (pin "9") (pinfunction "9_9") (pintype "passive"))
      (node (ref "D403") (pin "3") (pinfunction "3_3") (pintype "passive"))
      (node (ref "R407") (pin "1") (pinfunction "1_1") (pintype "passive"))
    )
    (net (code "64") (name "Net-(CON401-CLKREQ#)") (class "Default")
      (node (ref "CON401") (pin "7") (pinfunction "CLKREQ#_7") (pintype "output"))
      (node (ref "R414") (pin "1") (pinfunction "1_1") (pintype "passive"))
    )
    (net (code "65") (name "Net-(CON401-PERST#)") (class "Default")
      (node (ref "CON401") (pin "22") (pinfunction "PERST#_22") (pintype "input"))
      (node (ref "R413") (pin "1") (pinfunction "1_1") (pintype "passive"))
    )
    (net (code "66") (name "Net-(CON401-SMB_CLK)") (class "Default")
      (node (ref "CON401") (pin "30") (pinfunction "SMB_CLK_30") (pintype "input"))
      (node (ref "R428") (pin "2") (pinfunction "2_2") (pintype "passive"))
    )
    (net (code "67") (name "Net-(CON401-SMB_DAT)") (class "Default")
      (node (ref "CON401") (pin "32") (pinfunction "SMB_DAT_32") (pintype "bidirectional"))
      (node (ref "R429") (pin "2") (pinfunction "2_2") (pintype "passive"))
    )
    (net (code "68") (name "Net-(CON401-USB_D+)") (class "Default")
      (node (ref "CON401") (pin "38") (pinfunction "USB_D+_38") (pintype "bidirectional"))
      (node (ref "L404") (pin "2") (pinfunction "2_2") (pintype "passive"))
    )
    (net (code "69") (name "Net-(CON401-USB_D-)") (class "Default")
      (node (ref "CON401") (pin "36") (pinfunction "USB_D-_36") (pintype "bidirectional"))
      (node (ref "L404") (pin "3") (pinfunction "3_3") (pintype "passive"))
    )
    (net (code "70") (name "Net-(CON401-WAKE#)") (class "Default")
      (node (ref "CON401") (pin "1") (pinfunction "WAKE#_1") (pintype "output"))
      (node (ref "R412") (pin "1") (pinfunction "1_1") (pintype "passive"))
    )
    (net (code "71") (name "Net-(CON401-W_DISABLE#)") (class "Default")
      (node (ref "CON401") (pin "20") (pinfunction "W_DISABLE#_20") (pintype "input"))
      (node (ref "R409") (pin "1") (pinfunction "1_1") (pintype "passive"))
    )
    (net (code "72") (name "Net-(CON402-0)") (class "Default")
      (node (ref "CON402") (pin "1") (pinfunction "0_1") (pintype "passive"))
      (node (ref "L400") (pin "1") (pinfunction "1_1") (pintype "passive"))
    )
    (net (code "73") (name "Net-(CON403-0)") (class "Default")
      (node (ref "CON403") (pin "1") (pinfunction "0_1") (pintype "passive"))
      (node (ref "L405") (pin "1") (pinfunction "1_1") (pintype "passive"))
    )
    (net (code "74") (name "Net-(D400-A)") (class "Default")
      (node (ref "D400") (pin "1") (pinfunction "A_1") (pintype "passive"))
      (node (ref "R401") (pin "1") (pinfunction "1_1") (pintype "passive"))
    )
    (net (code "75") (name "Net-(D401-A)") (class "Default")
      (node (ref "D401") (pin "1") (pinfunction "A_1") (pintype "passive"))
      (node (ref "R400") (pin "1") (pinfunction "1_1") (pintype "passive"))
    )
    (net (code "76") (name "Net-(D402-A)") (class "Default")
      (node (ref "D402") (pin "1") (pinfunction "A_1") (pintype "passive"))
      (node (ref "R402") (pin "1") (pinfunction "1_1") (pintype "passive"))
    )
    (net (code "77") (name "Net-(Q400-D)") (class "Default")
      (node (ref "Q400") (pin "3") (pinfunction "D_3") (pintype "passive"))
      (node (ref "U400") (pin "22") (pinfunction "~{CKPWRGD_PD}_22") (pintype "input"))
    )
    (net (code "78") (name "Net-(Q400-G)") (class "Default")
      (node (ref "D404") (pin "A") (pinfunction "A_A") (pintype "passive"))
      (node (ref "Q400") (pin "1") (pinfunction "G_1") (pintype "passive"))
      (node (ref "R421") (pin "1") (pinfunction "1_1") (pintype "passive"))
      (node (ref "R427") (pin "2") (pinfunction "2_2") (pintype "passive"))
    )
    (net (code "79") (name "Net-(U400-VDD1.8_1)") (class "Default")
      (node (ref "C409") (pin "1") (pinfunction "1_1") (pintype "passive"))
      (node (ref "C410") (pin "1") (pinfunction "1_1") (pintype "passive"))
      (node (ref "C411") (pin "1") (pinfunction "1_1") (pintype "passive"))
      (node (ref "L403") (pin "2") (pinfunction "2_2") (pintype "passive"))
      (node (ref "U400") (pin "11") (pinfunction "VDD1.8_1_11") (pintype "power_in"))
      (node (ref "U400") (pin "20") (pinfunction "VDD1.8_2_20") (pintype "power_in"))
    )
    (net (code "80") (name "Net-(U400-VDDA1.8)") (class "Default")
      (node (ref "C406") (pin "1") (pinfunction "1_1") (pintype "passive"))
      (node (ref "C407") (pin "1") (pinfunction "1_1") (pintype "passive"))
      (node (ref "C408") (pin "1") (pinfunction "1_1") (pintype "passive"))
      (node (ref "L402") (pin "1") (pinfunction "1_1") (pintype "passive"))
      (node (ref "U400") (pin "16") (pinfunction "VDDA1.8_16") (pintype "power_in"))
      (node (ref "U400") (pin "3") (pinfunction "VDDXTAL1.8_3") (pintype "power_in"))
    )
    (net (code "81") (name "Net-(U400-VDDDIG1.8)") (class "Default")
      (node (ref "C404") (pin "1") (pinfunction "1_1") (pintype "passive"))
      (node (ref "C405") (pin "1") (pinfunction "1_1") (pintype "passive"))
      (node (ref "L401") (pin "2") (pinfunction "2_2") (pintype "passive"))
      (node (ref "U400") (pin "7") (pinfunction "VDDDIG1.8_7") (pintype "power_in"))
    )
    (net (code "82") (name "Net-(U400-X1_25)") (class "Default")
      (node (ref "C412") (pin "2") (pinfunction "2_2") (pintype "passive"))
      (node (ref "U400") (pin "1") (pinfunction "X1_25_1") (pintype "input"))
      (node (ref "XTAL400") (pin "1") (pinfunction "1_1") (pintype "passive"))
    )
    (net (code "83") (name "Net-(U400-X2)") (class "Default")
      (node (ref "C417") (pin "2") (pinfunction "2_2") (pintype "passive"))
      (node (ref "U400") (pin "2") (pinfunction "X2_2") (pintype "output"))
      (node (ref "XTAL400") (pin "3") (pinfunction "3_3") (pintype "passive"))
    )
    (net (code "84") (name "unconnected-(CON400-Pad4)") (class "Default")
      (node (ref "CON400") (pin "4") (pinfunction "4_4") (pintype "passive"))
    )
    (net (code "85") (name "unconnected-(CON400-Pad6)") (class "Default")
      (node (ref "CON400") (pin "6") (pinfunction "6_6") (pintype "passive"))
    )
    (net (code "86") (name "unconnected-(CON400-Pad8)") (class "Default")
      (node (ref "CON400") (pin "8") (pinfunction "8_8") (pintype "passive"))
    )
    (net (code "87") (name "unconnected-(CON401-COEX1-Pad3)") (class "Default")
      (node (ref "CON401") (pin "3") (pinfunction "COEX1_3") (pintype "passive+no_connect"))
    )
    (net (code "88") (name "unconnected-(CON401-COEX2-Pad5)") (class "Default")
      (node (ref "CON401") (pin "5") (pinfunction "COEX2_5") (pintype "passive+no_connect"))
    )
    (net (code "89") (name "unconnected-(CON401-RSVD-Pad45)") (class "Default")
      (node (ref "CON401") (pin "45") (pinfunction "RSVD_45") (pintype "passive+no_connect"))
    )
    (net (code "90") (name "unconnected-(CON401-RSVD-Pad47)") (class "Default")
      (node (ref "CON401") (pin "47") (pinfunction "RSVD_47") (pintype "passive+no_connect"))
    )
    (net (code "91") (name "unconnected-(CON401-RSVD-Pad49)") (class "Default")
      (node (ref "CON401") (pin "49") (pinfunction "RSVD_49") (pintype "passive+no_connect"))
    )
    (net (code "92") (name "unconnected-(CON401-RSVD-Pad51)") (class "Default")
      (node (ref "CON401") (pin "51") (pinfunction "RSVD_51") (pintype "passive+no_connect"))
    )
    (net (code "93") (name "unconnected-(CON401-SIM_C4{slash}RSVD-Pad19)") (class "Default")
      (node (ref "CON401") (pin "19") (pinfunction "SIM_C4/RSVD_19") (pintype "bidirectional"))
    )
    (net (code "94") (name "unconnected-(CON401-SIM_C8{slash}RSVD-Pad17)") (class "Default")
      (node (ref "CON401") (pin "17") (pinfunction "SIM_C8/RSVD_17") (pintype "bidirectional"))
    )
    (net (code "95") (name "unconnected-(CON401-UIM_VPP-Pad16)") (class "Default")
      (node (ref "CON401") (pin "16") (pinfunction "UIM_VPP_16") (pintype "output"))
    )
  )
)
